# v2.net
KiCad netlist of a schematic drawn in EAGLE
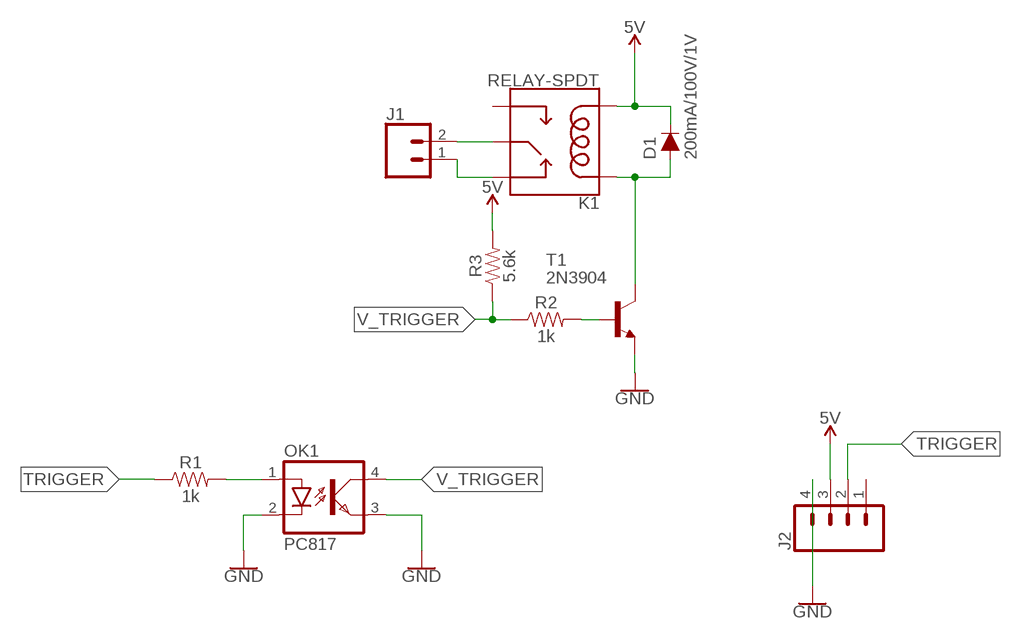
[diagram p0: schematic, sheet 1]

(export (version "E")
  (design (tool "Eeschema 10.0.6"))
  (components
    (comp (ref "D1")
      (value "200mA/100V/1V")
      (footprint "eagle-import:DIODE-1N4148-KIT")
      (libsource (lib "eagle-import") (part "DIODE-KIT"))
    )
    (comp (ref "J1")
      (value "CONN_025MM")
      (footprint "eagle-import:SCREWTERMINAL-5MM-2")
      (libsource (lib "eagle-import") (part "CONN_025MM"))
    )
    (comp (ref "J2")
      (value "CONN_04")
      (footprint "eagle-import:1X04")
      (libsource (lib "eagle-import") (part "CONN_04"))
    )
    (comp (ref "K1")
      (value "RELAY-SPDT")
      (footprint "eagle-import:RELAY_G5LE")
      (libsource (lib "eagle-import") (part "RELAY-SPDT"))
    )
    (comp (ref "OK1")
      (value "PC817")
      (footprint "eagle-import:DIL04")
      (fields (field (name "MPN") "PC817X4J000F"))
      (libsource (lib "eagle-import") (part "PC817"))
    )
    (comp (ref "R1")
      (value "1k")
      (footprint "eagle-import:AXIAL-0.3")
      (libsource (lib "eagle-import") (part "SparkFun-Resistors_532_1KOHM-HORIZ-1/4W-1%"))
    )
    (comp (ref "R2")
      (value "1k")
      (footprint "eagle-import:AXIAL-0.3")
      (libsource (lib "eagle-import") (part "1KOHM-HORIZ-1/4W-1%"))
    )
    (comp (ref "R3")
      (value "5.6k")
      (footprint "eagle-import:AXIAL-0.3")
      (libsource (lib "eagle-import") (part "1KOHM-HORIZ-1/4W-1%"))
    )
    (comp (ref "T1")
      (value "2N3904")
      (footprint "eagle-import:TO92")
      (libsource (lib "eagle-import") (part "2N3904"))
    )
  )
  (nets
    (net (code "1") (name "5V") (class "Default")
      (node (ref "D1") (pin "C") (pinfunction "C_C") (pintype "passive"))
      (node (ref "J2") (pin "3") (pinfunction "3_3") (pintype "passive"))
      (node (ref "K1") (pin "5") (pinfunction "COIL2_5") (pintype "bidirectional"))
      (node (ref "R3") (pin "P$2") (pinfunction "2_P$2") (pintype "passive"))
    )
    (net (code "2") (name "GND") (class "Default")
      (node (ref "J2") (pin "4") (pinfunction "4_4") (pintype "passive"))
      (node (ref "OK1") (pin "2") (pinfunction "C_2") (pintype "passive"))
      (node (ref "OK1") (pin "3") (pinfunction "EMIT_3") (pintype "passive"))
      (node (ref "T1") (pin "3") (pinfunction "E_3") (pintype "passive"))
    )
    (net (code "3") (name "Net-(K1-COIL1)") (class "Default")
      (node (ref "D1") (pin "A") (pinfunction "A_A") (pintype "passive"))
      (node (ref "K1") (pin "2") (pinfunction "COIL1_2") (pintype "bidirectional"))
      (node (ref "T1") (pin "1") (pinfunction "C_1") (pintype "passive"))
    )
    (net (code "4") (name "Net-(K1-MAIN)") (class "Default")
      (node (ref "J1") (pin "2") (pinfunction "2_2") (pintype "passive"))
      (node (ref "K1") (pin "1") (pinfunction "MAIN_1") (pintype "bidirectional"))
    )
    (net (code "5") (name "Net-(K1-NC)") (class "Default")
      (node (ref "J1") (pin "1") (pinfunction "1_1") (pintype "passive"))
      (node (ref "K1") (pin "4") (pinfunction "NC_4") (pintype "bidirectional"))
    )
    (net (code "6") (name "Net-(OK1-A)") (class "Default")
      (node (ref "OK1") (pin "1") (pinfunction "A_1") (pintype "passive"))
      (node (ref "R1") (pin "P$2") (pinfunction "2_P$2") (pintype "passive"))
    )
    (net (code "7") (name "Net-(R2-2)") (class "Default")
      (node (ref "R2") (pin "P$2") (pinfunction "2_P$2") (pintype "passive"))
      (node (ref "T1") (pin "2") (pinfunction "B_2") (pintype "passive"))
    )
    (net (code "8") (name "TRIGGER") (class "Default")
      (node (ref "J2") (pin "2") (pinfunction "2_2") (pintype "passive"))
      (node (ref "R1") (pin "P$1") (pinfunction "1_P$1") (pintype "passive"))
    )
    (net (code "9") (name "V_TRIGGER") (class "Default")
      (node (ref "OK1") (pin "4") (pinfunction "COL_4") (pintype "passive"))
      (node (ref "R2") (pin "P$1") (pinfunction "1_P$1") (pintype "passive"))
      (node (ref "R3") (pin "P$1") (pinfunction "1_P$1") (pintype "passive"))
    )
    (net (code "10") (name "unconnected-(J2-Pad1)") (class "Default")
      (node (ref "J2") (pin "1") (pinfunction "1_1") (pintype "passive"))
    )
    (net (code "11") (name "unconnected-(K1-NO-Pad3)") (class "Default")
      (node (ref "K1") (pin "3") (pinfunction "NO_3") (pintype "bidirectional"))
    )
  )
)
